# DUAL_SLOPE_ADC.net
KiCad netlist of a schematic drawn in EasyEDA Pro
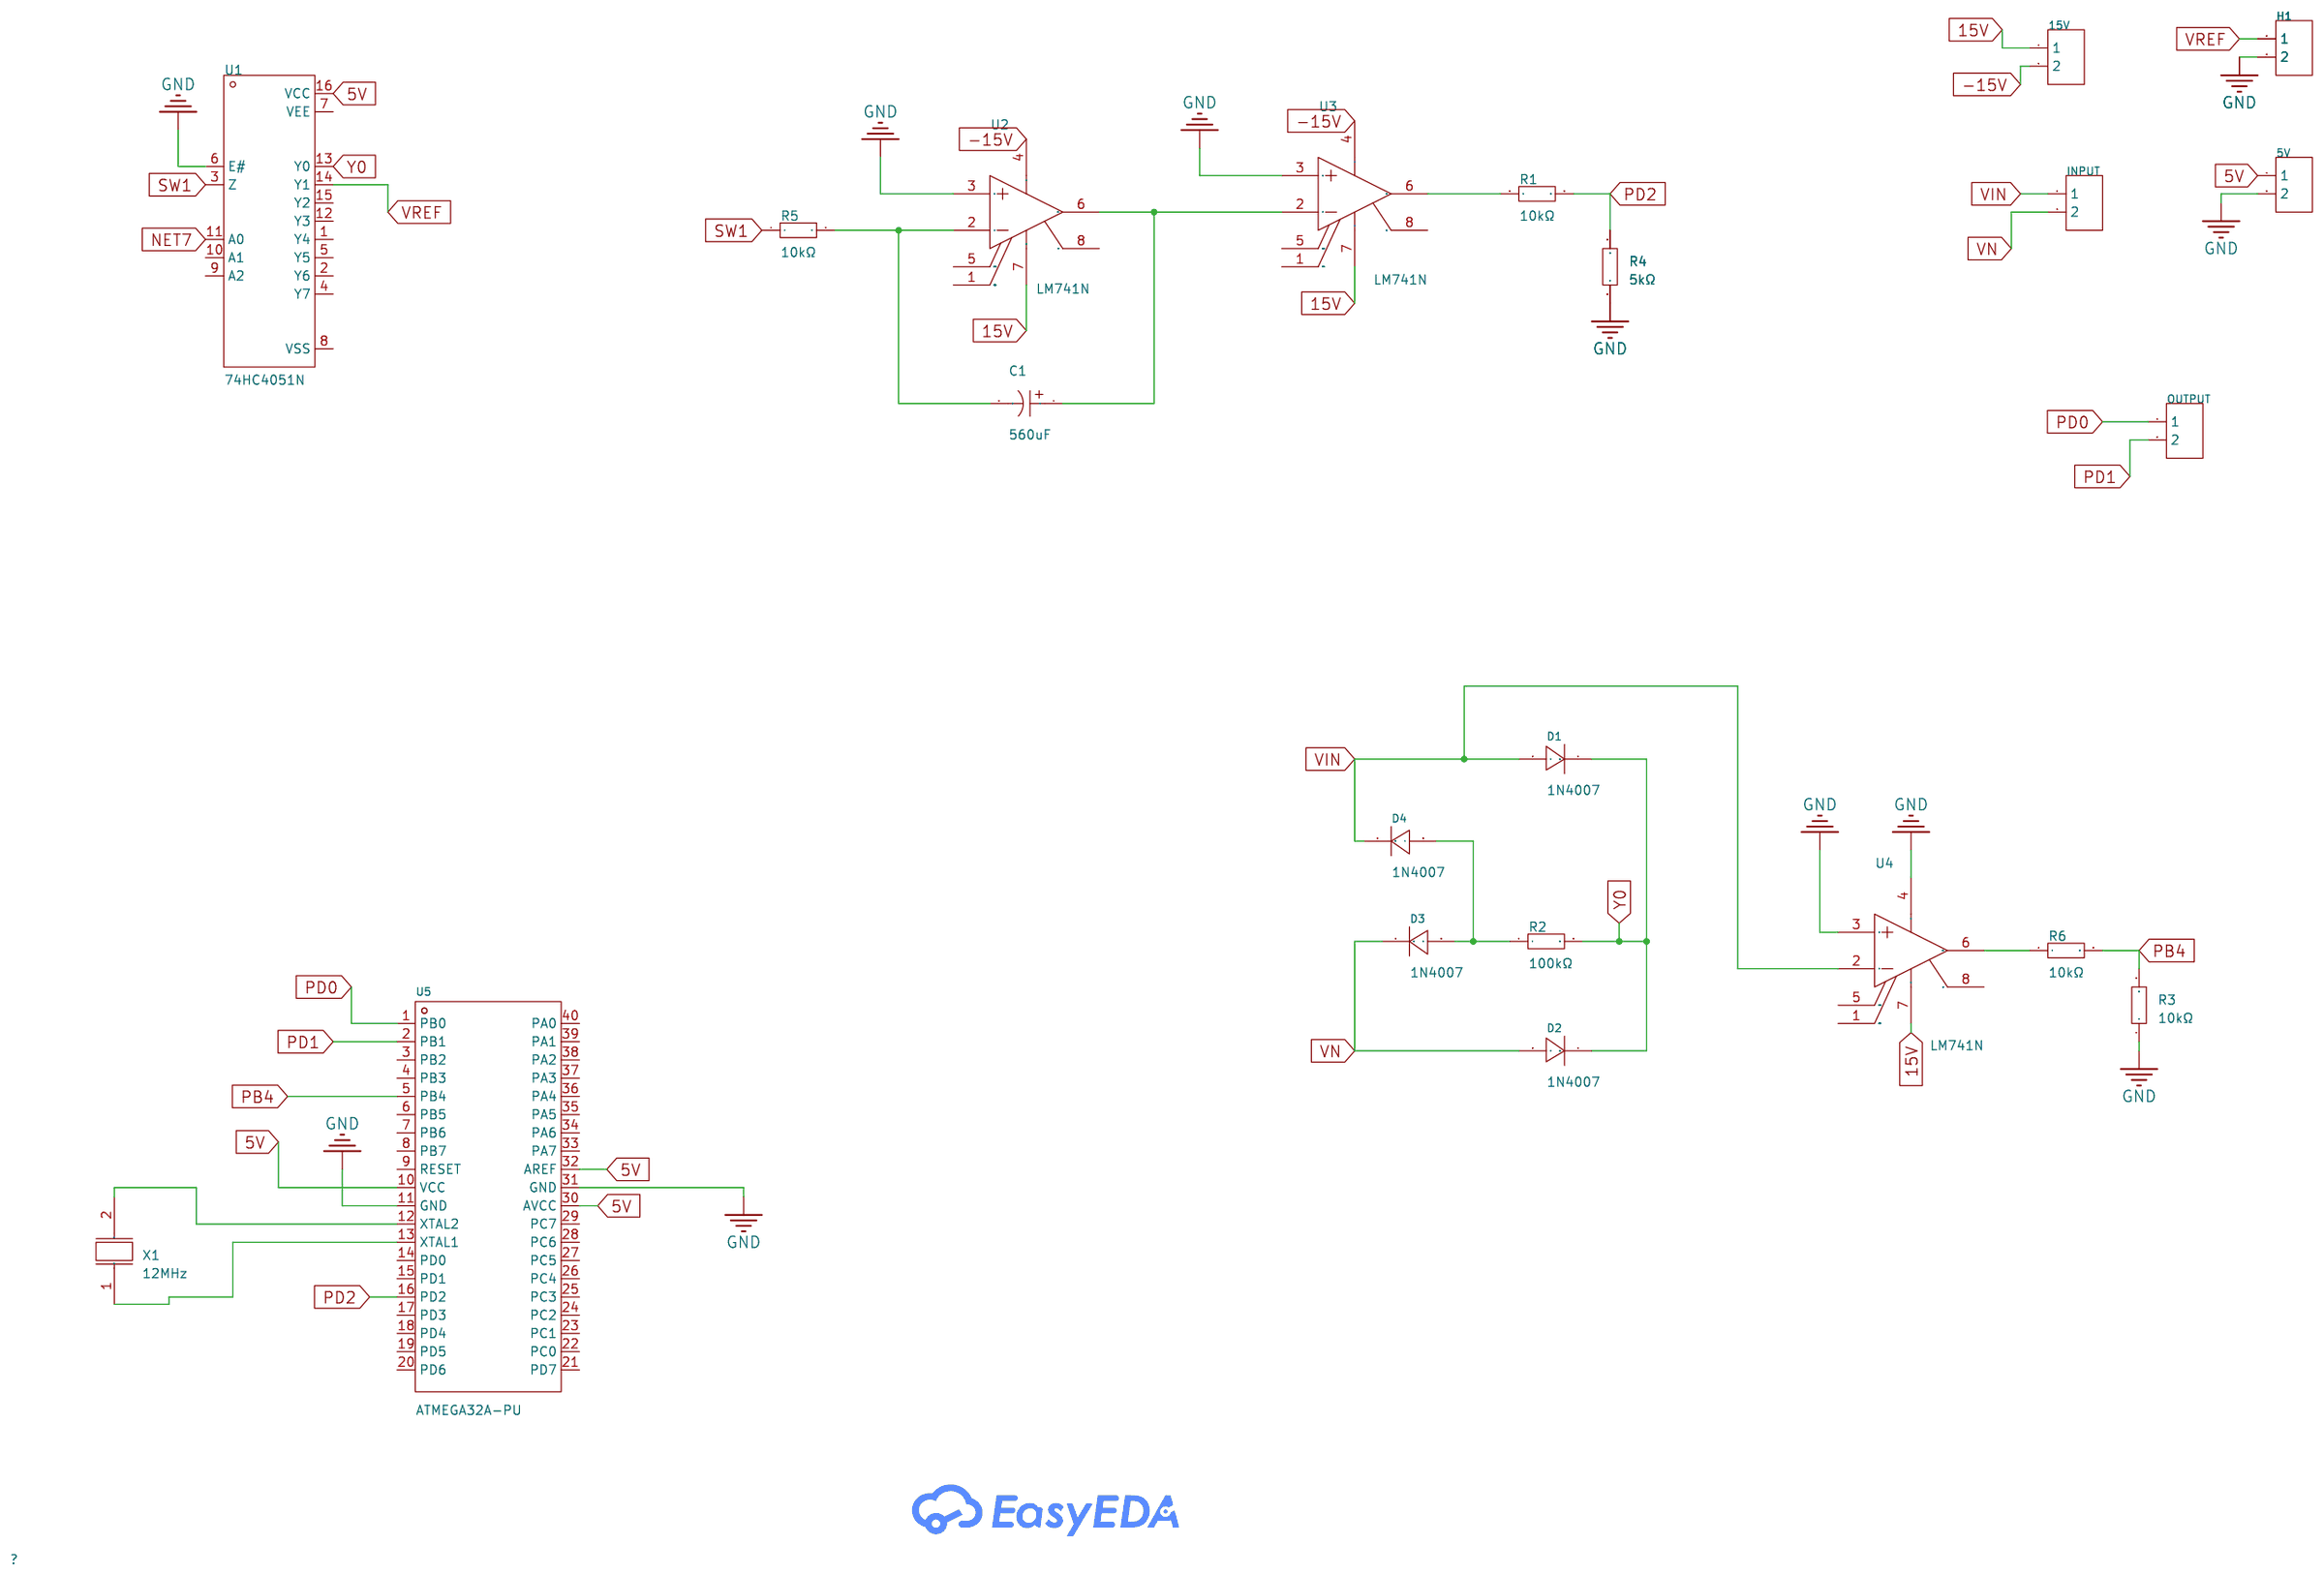
[diagram p0: schematic sheet]

(export (version "E")
  (design (tool "Eeschema 10.0.6"))
  (components
    (comp (ref "5V")
      (value "~")
      (footprint "easyedapro:HDR-TH_2P-P2.54-V-F")
      (libsource (lib "easyedapro") (part "Header-Female-2.54_1x2"))
    )
    (comp (ref "15V")
      (value "~")
      (footprint "easyedapro:HDR-TH_2P-P2.54-V-F")
      (libsource (lib "easyedapro") (part "Header-Female-2.54_1x2"))
    )
    (comp (ref "C1")
      (value "560uF")
      (footprint "easyedapro:CAP-TH_BD6.3-P2.50-D1.0-FD_1")
      (fields
        (field (name "Manufacturer Part") "DHG010M567E120S1AA")
        (field (name "Manufacturer") "KNSCHA(科尼盛)")
      )
      (libsource (lib "easyedapro") (part "DHG010M567E120S1AA"))
    )
    (comp (ref "D1")
      (value "1N4007")
      (footprint "easyedapro:DO-41_BD2.4-L4.7-P8.70-D0.9-RD")
      (fields (field (name "Manufacturer") "GD(固锝)"))
      (libsource (lib "easyedapro") (part "1N4007_C193790"))
    )
    (comp (ref "D2")
      (value "1N4007")
      (footprint "easyedapro:DO-41_BD2.4-L4.7-P8.70-D0.9-RD")
      (fields (field (name "Manufacturer") "GD(固锝)"))
      (libsource (lib "easyedapro") (part "1N4007_C193790"))
    )
    (comp (ref "D3")
      (value "1N4007")
      (footprint "easyedapro:DO-41_BD2.4-L4.7-P8.70-D0.9-RD")
      (fields (field (name "Manufacturer") "GD(固锝)"))
      (libsource (lib "easyedapro") (part "1N4007_C193790"))
    )
    (comp (ref "D4")
      (value "1N4007")
      (footprint "easyedapro:DO-41_BD2.4-L4.7-P8.70-D0.9-RD")
      (fields (field (name "Manufacturer") "GD(固锝)"))
      (libsource (lib "easyedapro") (part "1N4007_C193790"))
    )
    (comp (ref "H1")
      (value "~")
      (footprint "easyedapro:HDR-TH_2P-P2.54-V-F")
      (libsource (lib "easyedapro") (part "Header-Female-2.54_1x2"))
    )
    (comp (ref "INPUT")
      (value "~")
      (footprint "easyedapro:HDR-TH_2P-P2.54-V-F")
      (libsource (lib "easyedapro") (part "Header-Female-2.54_1x2"))
    )
    (comp (ref "OUTPUT")
      (value "~")
      (footprint "easyedapro:HDR-TH_2P-P2.54-V-F")
      (libsource (lib "easyedapro") (part "Header-Female-2.54_1x2"))
    )
    (comp (ref "R1")
      (value "10kΩ")
      (footprint "easyedapro:RES-TH_BD1.8-L3.2-P7.20-D0.4")
      (libsource (lib "easyedapro") (part "Res"))
    )
    (comp (ref "R2")
      (value "100kΩ")
      (footprint "easyedapro:RES-TH_BD1.8-L3.2-P7.20-D0.4")
      (libsource (lib "easyedapro") (part "Res"))
    )
    (comp (ref "R3")
      (value "10kΩ")
      (footprint "easyedapro:RES-TH_BD1.8-L3.2-P7.20-D0.4")
      (libsource (lib "easyedapro") (part "Res"))
    )
    (comp (ref "R4")
      (value "5kΩ")
      (footprint "easyedapro:RES-TH_BD1.8-L3.2-P7.20-D0.4")
      (libsource (lib "easyedapro") (part "Res"))
    )
    (comp (ref "R5")
      (value "10kΩ")
      (footprint "easyedapro:RES-TH_BD1.8-L3.2-P7.20-D0.4")
      (libsource (lib "easyedapro") (part "Res"))
    )
    (comp (ref "R6")
      (value "10kΩ")
      (footprint "easyedapro:RES-TH_BD1.8-L3.2-P7.20-D0.4")
      (libsource (lib "easyedapro") (part "Res"))
    )
    (comp (ref "U1")
      (value "74HC4051N")
      (footprint "easyedapro:PDIP-16_L19.3-W6.4-P2.54-LS7.94-BL")
      (fields (field (name "Manufacturer") "HGSEMI(华冠)"))
      (libsource (lib "easyedapro") (part "74HC4051N"))
    )
    (comp (ref "U2")
      (value "LM741N")
      (footprint "easyedapro:DIP-8_L9.3-W6.4-P2.54-LS7.6-BL")
      (fields (field (name "Manufacturer") "HGSEMI(华冠)"))
      (libsource (lib "easyedapro") (part "LM741N"))
    )
    (comp (ref "U3")
      (value "LM741N")
      (footprint "easyedapro:DIP-8_L9.3-W6.4-P2.54-LS7.6-BL")
      (fields (field (name "Manufacturer") "HGSEMI(华冠)"))
      (libsource (lib "easyedapro") (part "LM741N"))
    )
    (comp (ref "U4")
      (value "LM741N")
      (footprint "easyedapro:DIP-8_L9.3-W6.4-P2.54-LS7.6-BL")
      (fields (field (name "Manufacturer") "HGSEMI(华冠)"))
      (libsource (lib "easyedapro") (part "LM741N"))
    )
    (comp (ref "U5")
      (value "ATMEGA32A-PU")
      (footprint "easyedapro:DIP-40_L52.3-W13.9-P2.54-LS15.2-BL")
      (fields (field (name "Manufacturer") "MICROCHIP(美国微芯)"))
      (libsource (lib "easyedapro") (part "ATMEGA32A-PU"))
    )
    (comp (ref "X1")
      (value "12MHz")
      (footprint "easyedapro:CRYSTAL-SMD_L5.0-W3.2-1-A")
      (libsource (lib "easyedapro") (part "12MHZ"))
    )
  )
  (nets
    (net (code "1") (name "-15V") (class "Default")
      (node (ref "15V") (pin "2") (pinfunction "2_2") (pintype "input"))
      (node (ref "U2") (pin "4") (pinfunction "V-_4") (pintype "unspecified"))
      (node (ref "U3") (pin "4") (pinfunction "V-_4") (pintype "unspecified"))
    )
    (net (code "2") (name "5V") (class "Default")
      (node (ref "5V") (pin "1") (pinfunction "1_1") (pintype "input"))
      (node (ref "U1") (pin "16") (pinfunction "VCC_16") (pintype "unspecified"))
      (node (ref "U5") (pin "10") (pinfunction "VCC_10") (pintype "input"))
      (node (ref "U5") (pin "30") (pinfunction "AVCC_30") (pintype "input"))
      (node (ref "U5") (pin "32") (pinfunction "AREF_32") (pintype "input"))
    )
    (net (code "3") (name "15V") (class "Default")
      (node (ref "15V") (pin "1") (pinfunction "1_1") (pintype "input"))
      (node (ref "U2") (pin "7") (pinfunction "V+_7") (pintype "unspecified"))
      (node (ref "U3") (pin "7") (pinfunction "V+_7") (pintype "unspecified"))
      (node (ref "U4") (pin "7") (pinfunction "V+_7") (pintype "unspecified"))
    )
    (net (code "4") (name "GND") (class "Default")
      (node (ref "5V") (pin "2") (pinfunction "2_2") (pintype "input"))
      (node (ref "H1") (pin "2") (pinfunction "2_2") (pintype "input"))
      (node (ref "R3") (pin "1") (pinfunction "1_1") (pintype "input"))
      (node (ref "R4") (pin "1") (pinfunction "1_1") (pintype "input"))
      (node (ref "U1") (pin "6") (pinfunction "E#_6") (pintype "unspecified"))
      (node (ref "U2") (pin "3") (pinfunction "+IN_3") (pintype "unspecified"))
      (node (ref "U3") (pin "3") (pinfunction "+IN_3") (pintype "unspecified"))
      (node (ref "U4") (pin "3") (pinfunction "+IN_3") (pintype "unspecified"))
      (node (ref "U4") (pin "4") (pinfunction "V-_4") (pintype "unspecified"))
      (node (ref "U5") (pin "11") (pinfunction "GND_11") (pintype "input"))
      (node (ref "U5") (pin "31") (pinfunction "GND_31") (pintype "input"))
    )
    (net (code "5") (name "NET7") (class "Default")
      (node (ref "U1") (pin "11") (pinfunction "A0_11") (pintype "unspecified"))
    )
    (net (code "6") (name "Net-(D3-A)") (class "Default")
      (node (ref "D3") (pin "2") (pinfunction "A_2") (pintype "input"))
      (node (ref "D4") (pin "2") (pinfunction "A_2") (pintype "input"))
      (node (ref "R2") (pin "1") (pinfunction "1_1") (pintype "input"))
    )
    (net (code "7") (name "Net-(U2--IN)") (class "Default")
      (node (ref "C1") (pin "2") (pinfunction "2_2") (pintype "input"))
      (node (ref "R5") (pin "2") (pinfunction "2_2") (pintype "input"))
      (node (ref "U2") (pin "2") (pinfunction "-IN_2") (pintype "unspecified"))
    )
    (net (code "8") (name "Net-(U2-OUT)") (class "Default")
      (node (ref "C1") (pin "1") (pinfunction "1_1") (pintype "input"))
      (node (ref "U2") (pin "6") (pinfunction "OUT_6") (pintype "output"))
      (node (ref "U3") (pin "2") (pinfunction "-IN_2") (pintype "unspecified"))
    )
    (net (code "9") (name "Net-(U3-OUT)") (class "Default")
      (node (ref "R1") (pin "1") (pinfunction "1_1") (pintype "input"))
      (node (ref "U3") (pin "6") (pinfunction "OUT_6") (pintype "output"))
    )
    (net (code "10") (name "Net-(U4-OUT)") (class "Default")
      (node (ref "R6") (pin "1") (pinfunction "1_1") (pintype "input"))
      (node (ref "U4") (pin "6") (pinfunction "OUT_6") (pintype "output"))
    )
    (net (code "11") (name "Net-(U5-XTAL1)") (class "Default")
      (node (ref "U5") (pin "13") (pinfunction "XTAL1_13") (pintype "input"))
      (node (ref "X1") (pin "1") (pinfunction "1_1") (pintype "unspecified"))
    )
    (net (code "12") (name "Net-(U5-XTAL2)") (class "Default")
      (node (ref "U5") (pin "12") (pinfunction "XTAL2_12") (pintype "input"))
      (node (ref "X1") (pin "2") (pinfunction "2_2") (pintype "unspecified"))
    )
    (net (code "13") (name "PB4") (class "Default")
      (node (ref "R3") (pin "2") (pinfunction "2_2") (pintype "input"))
      (node (ref "R6") (pin "2") (pinfunction "2_2") (pintype "input"))
      (node (ref "U5") (pin "5") (pinfunction "PB4_5") (pintype "input"))
    )
    (net (code "14") (name "PD0") (class "Default")
      (node (ref "OUTPUT") (pin "1") (pinfunction "1_1") (pintype "input"))
      (node (ref "U5") (pin "1") (pinfunction "PB0_1") (pintype "input"))
    )
    (net (code "15") (name "PD1") (class "Default")
      (node (ref "OUTPUT") (pin "2") (pinfunction "2_2") (pintype "input"))
      (node (ref "U5") (pin "2") (pinfunction "PB1_2") (pintype "input"))
    )
    (net (code "16") (name "PD2") (class "Default")
      (node (ref "R1") (pin "2") (pinfunction "2_2") (pintype "input"))
      (node (ref "R4") (pin "2") (pinfunction "2_2") (pintype "input"))
      (node (ref "U5") (pin "16") (pinfunction "PD2_16") (pintype "input"))
    )
    (net (code "17") (name "SW1") (class "Default")
      (node (ref "R5") (pin "1") (pinfunction "1_1") (pintype "input"))
      (node (ref "U1") (pin "3") (pinfunction "Z_3") (pintype "unspecified"))
    )
    (net (code "18") (name "VIN") (class "Default")
      (node (ref "D1") (pin "2") (pinfunction "A_2") (pintype "input"))
      (node (ref "D4") (pin "1") (pinfunction "C_1") (pintype "input"))
      (node (ref "INPUT") (pin "1") (pinfunction "1_1") (pintype "input"))
      (node (ref "U4") (pin "2") (pinfunction "-IN_2") (pintype "unspecified"))
    )
    (net (code "19") (name "VN") (class "Default")
      (node (ref "D2") (pin "2") (pinfunction "A_2") (pintype "input"))
      (node (ref "D3") (pin "1") (pinfunction "C_1") (pintype "input"))
      (node (ref "INPUT") (pin "2") (pinfunction "2_2") (pintype "input"))
    )
    (net (code "20") (name "VREF") (class "Default")
      (node (ref "H1") (pin "1") (pinfunction "1_1") (pintype "input"))
      (node (ref "U1") (pin "14") (pinfunction "Y1_14") (pintype "unspecified"))
    )
    (net (code "21") (name "Y0") (class "Default")
      (node (ref "D1") (pin "1") (pinfunction "C_1") (pintype "input"))
      (node (ref "D2") (pin "1") (pinfunction "C_1") (pintype "input"))
      (node (ref "R2") (pin "2") (pinfunction "2_2") (pintype "input"))
      (node (ref "U1") (pin "13") (pinfunction "Y0_13") (pintype "unspecified"))
    )
    (net (code "22") (name "unconnected-(U1-A1-Pad10)") (class "Default")
      (node (ref "U1") (pin "10") (pinfunction "A1_10") (pintype "unspecified"))
    )
    (net (code "23") (name "unconnected-(U1-A2-Pad9)") (class "Default")
      (node (ref "U1") (pin "9") (pinfunction "A2_9") (pintype "unspecified"))
    )
    (net (code "24") (name "unconnected-(U1-VEE-Pad7)") (class "Default")
      (node (ref "U1") (pin "7") (pinfunction "VEE_7") (pintype "unspecified"))
    )
    (net (code "25") (name "unconnected-(U1-VSS-Pad8)") (class "Default")
      (node (ref "U1") (pin "8") (pinfunction "VSS_8") (pintype "unspecified"))
    )
    (net (code "26") (name "unconnected-(U1-Y2-Pad15)") (class "Default")
      (node (ref "U1") (pin "15") (pinfunction "Y2_15") (pintype "unspecified"))
    )
    (net (code "27") (name "unconnected-(U1-Y3-Pad12)") (class "Default")
      (node (ref "U1") (pin "12") (pinfunction "Y3_12") (pintype "unspecified"))
    )
    (net (code "28") (name "unconnected-(U1-Y4-Pad1)") (class "Default")
      (node (ref "U1") (pin "1") (pinfunction "Y4_1") (pintype "unspecified"))
    )
    (net (code "29") (name "unconnected-(U1-Y5-Pad5)") (class "Default")
      (node (ref "U1") (pin "5") (pinfunction "Y5_5") (pintype "unspecified"))
    )
    (net (code "30") (name "unconnected-(U1-Y6-Pad2)") (class "Default")
      (node (ref "U1") (pin "2") (pinfunction "Y6_2") (pintype "unspecified"))
    )
    (net (code "31") (name "unconnected-(U1-Y7-Pad4)") (class "Default")
      (node (ref "U1") (pin "4") (pinfunction "Y7_4") (pintype "unspecified"))
    )
    (net (code "32") (name "unconnected-(U2-NC-Pad8)") (class "Default")
      (node (ref "U2") (pin "8") (pinfunction "NC_8") (pintype "unspecified"))
    )
    (net (code "33") (name "unconnected-(U2-OFFSET_NULL-Pad1)") (class "Default")
      (node (ref "U2") (pin "1") (pinfunction "OFFSET_NULL_1") (pintype "unspecified"))
    )
    (net (code "34") (name "unconnected-(U2-OFFSET_NULL-Pad5)") (class "Default")
      (node (ref "U2") (pin "5") (pinfunction "OFFSET_NULL_5") (pintype "unspecified"))
    )
    (net (code "35") (name "unconnected-(U3-NC-Pad8)") (class "Default")
      (node (ref "U3") (pin "8") (pinfunction "NC_8") (pintype "unspecified"))
    )
    (net (code "36") (name "unconnected-(U3-OFFSET_NULL-Pad1)") (class "Default")
      (node (ref "U3") (pin "1") (pinfunction "OFFSET_NULL_1") (pintype "unspecified"))
    )
    (net (code "37") (name "unconnected-(U3-OFFSET_NULL-Pad5)") (class "Default")
      (node (ref "U3") (pin "5") (pinfunction "OFFSET_NULL_5") (pintype "unspecified"))
    )
    (net (code "38") (name "unconnected-(U4-NC-Pad8)") (class "Default")
      (node (ref "U4") (pin "8") (pinfunction "NC_8") (pintype "unspecified"))
    )
    (net (code "39") (name "unconnected-(U4-OFFSET_NULL-Pad1)") (class "Default")
      (node (ref "U4") (pin "1") (pinfunction "OFFSET_NULL_1") (pintype "unspecified"))
    )
    (net (code "40") (name "unconnected-(U4-OFFSET_NULL-Pad5)") (class "Default")
      (node (ref "U4") (pin "5") (pinfunction "OFFSET_NULL_5") (pintype "unspecified"))
    )
    (net (code "41") (name "unconnected-(U5-PA0-Pad40)") (class "Default")
      (node (ref "U5") (pin "40") (pinfunction "PA0_40") (pintype "input"))
    )
    (net (code "42") (name "unconnected-(U5-PA1-Pad39)") (class "Default")
      (node (ref "U5") (pin "39") (pinfunction "PA1_39") (pintype "input"))
    )
    (net (code "43") (name "unconnected-(U5-PA2-Pad38)") (class "Default")
      (node (ref "U5") (pin "38") (pinfunction "PA2_38") (pintype "input"))
    )
    (net (code "44") (name "unconnected-(U5-PA3-Pad37)") (class "Default")
      (node (ref "U5") (pin "37") (pinfunction "PA3_37") (pintype "input"))
    )
    (net (code "45") (name "unconnected-(U5-PA4-Pad36)") (class "Default")
      (node (ref "U5") (pin "36") (pinfunction "PA4_36") (pintype "input"))
    )
    (net (code "46") (name "unconnected-(U5-PA5-Pad35)") (class "Default")
      (node (ref "U5") (pin "35") (pinfunction "PA5_35") (pintype "input"))
    )
    (net (code "47") (name "unconnected-(U5-PA6-Pad34)") (class "Default")
      (node (ref "U5") (pin "34") (pinfunction "PA6_34") (pintype "input"))
    )
    (net (code "48") (name "unconnected-(U5-PA7-Pad33)") (class "Default")
      (node (ref "U5") (pin "33") (pinfunction "PA7_33") (pintype "input"))
    )
    (net (code "49") (name "unconnected-(U5-PB2-Pad3)") (class "Default")
      (node (ref "U5") (pin "3") (pinfunction "PB2_3") (pintype "input"))
    )
    (net (code "50") (name "unconnected-(U5-PB3-Pad4)") (class "Default")
      (node (ref "U5") (pin "4") (pinfunction "PB3_4") (pintype "input"))
    )
    (net (code "51") (name "unconnected-(U5-PB5-Pad6)") (class "Default")
      (node (ref "U5") (pin "6") (pinfunction "PB5_6") (pintype "input"))
    )
    (net (code "52") (name "unconnected-(U5-PB6-Pad7)") (class "Default")
      (node (ref "U5") (pin "7") (pinfunction "PB6_7") (pintype "input"))
    )
    (net (code "53") (name "unconnected-(U5-PB7-Pad8)") (class "Default")
      (node (ref "U5") (pin "8") (pinfunction "PB7_8") (pintype "input"))
    )
    (net (code "54") (name "unconnected-(U5-PC0-Pad22)") (class "Default")
      (node (ref "U5") (pin "22") (pinfunction "PC0_22") (pintype "input"))
    )
    (net (code "55") (name "unconnected-(U5-PC1-Pad23)") (class "Default")
      (node (ref "U5") (pin "23") (pinfunction "PC1_23") (pintype "input"))
    )
    (net (code "56") (name "unconnected-(U5-PC2-Pad24)") (class "Default")
      (node (ref "U5") (pin "24") (pinfunction "PC2_24") (pintype "input"))
    )
    (net (code "57") (name "unconnected-(U5-PC3-Pad25)") (class "Default")
      (node (ref "U5") (pin "25") (pinfunction "PC3_25") (pintype "input"))
    )
    (net (code "58") (name "unconnected-(U5-PC4-Pad26)") (class "Default")
      (node (ref "U5") (pin "26") (pinfunction "PC4_26") (pintype "input"))
    )
    (net (code "59") (name "unconnected-(U5-PC5-Pad27)") (class "Default")
      (node (ref "U5") (pin "27") (pinfunction "PC5_27") (pintype "input"))
    )
    (net (code "60") (name "unconnected-(U5-PC6-Pad28)") (class "Default")
      (node (ref "U5") (pin "28") (pinfunction "PC6_28") (pintype "input"))
    )
    (net (code "61") (name "unconnected-(U5-PC7-Pad29)") (class "Default")
      (node (ref "U5") (pin "29") (pinfunction "PC7_29") (pintype "input"))
    )
    (net (code "62") (name "unconnected-(U5-PD0-Pad14)") (class "Default")
      (node (ref "U5") (pin "14") (pinfunction "PD0_14") (pintype "input"))
    )
    (net (code "63") (name "unconnected-(U5-PD1-Pad15)") (class "Default")
      (node (ref "U5") (pin "15") (pinfunction "PD1_15") (pintype "input"))
    )
    (net (code "64") (name "unconnected-(U5-PD3-Pad17)") (class "Default")
      (node (ref "U5") (pin "17") (pinfunction "PD3_17") (pintype "input"))
    )
    (net (code "65") (name "unconnected-(U5-PD4-Pad18)") (class "Default")
      (node (ref "U5") (pin "18") (pinfunction "PD4_18") (pintype "input"))
    )
    (net (code "66") (name "unconnected-(U5-PD5-Pad19)") (class "Default")
      (node (ref "U5") (pin "19") (pinfunction "PD5_19") (pintype "input"))
    )
    (net (code "67") (name "unconnected-(U5-PD6-Pad20)") (class "Default")
      (node (ref "U5") (pin "20") (pinfunction "PD6_20") (pintype "input"))
    )
    (net (code "68") (name "unconnected-(U5-PD7-Pad21)") (class "Default")
      (node (ref "U5") (pin "21") (pinfunction "PD7_21") (pintype "input"))
    )
    (net (code "69") (name "unconnected-(U5-RESET-Pad9)") (class "Default")
      (node (ref "U5") (pin "9") (pinfunction "RESET_9") (pintype "input"))
    )
  )
)
